# PCM1794_DAC_Breakout.net
KiCad netlist of a schematic drawn in EAGLE
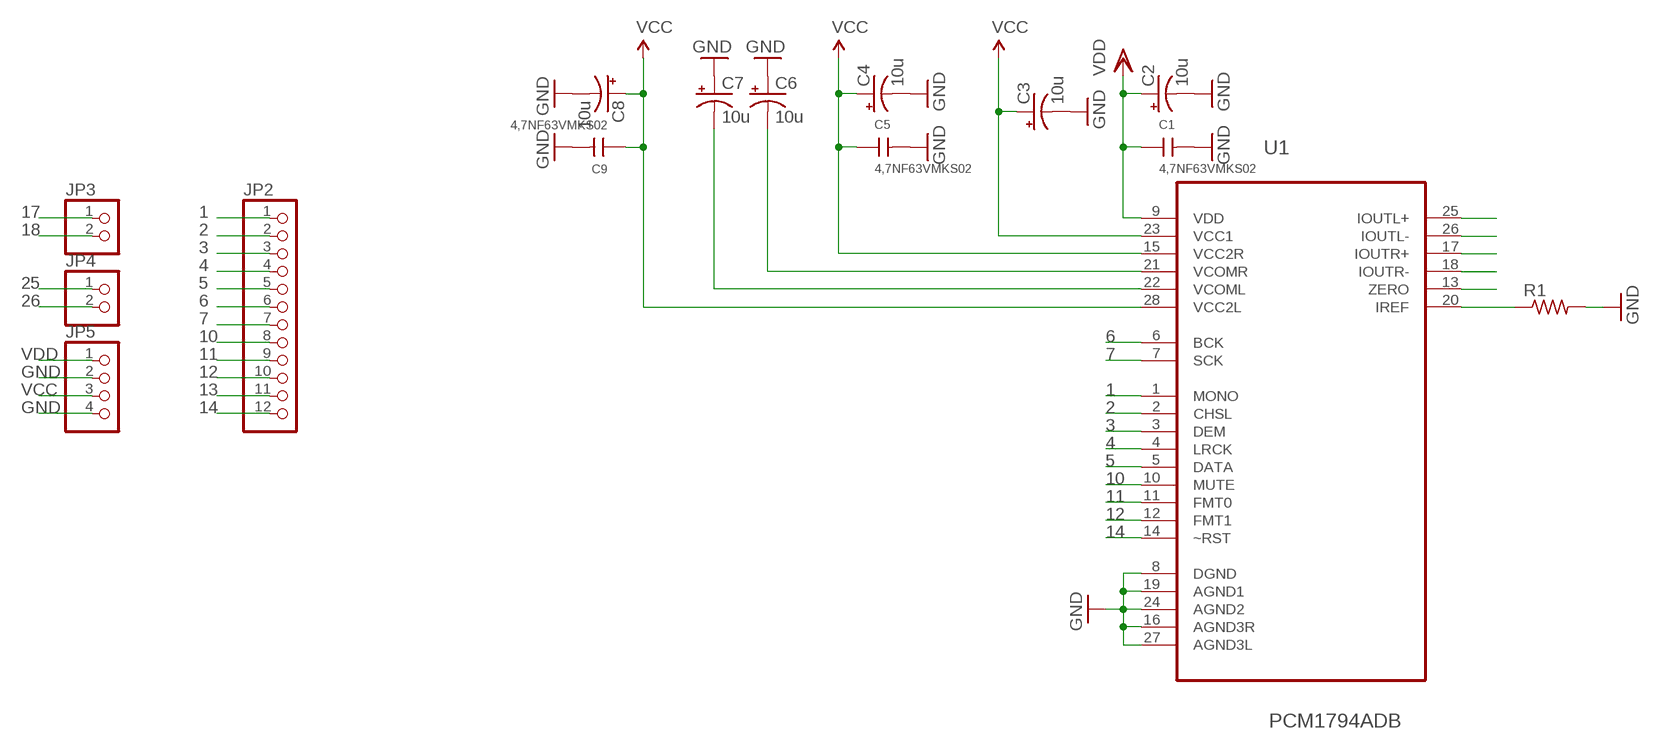
[diagram p0: schematic, sheet 1]

(export (version "E")
  (design (tool "Eeschema 10.0.6"))
  (components
    (comp (ref "C1")
      (value "4,7NF63VMKS02")
      (footprint "eagle-import:2,5X7,0RM2,5")
      (libsource (lib "eagle-import") (part "4,7NF63VMKS02"))
    )
    (comp (ref "C2")
      (value "10u")
      (footprint "eagle-import:E2,5-6")
      (libsource (lib "eagle-import") (part "CPOL-USE2.5-6"))
    )
    (comp (ref "C3")
      (value "10u")
      (footprint "eagle-import:E2,5-6")
      (libsource (lib "eagle-import") (part "CPOL-USE2.5-6"))
    )
    (comp (ref "C4")
      (value "10u")
      (footprint "eagle-import:E2,5-6")
      (libsource (lib "eagle-import") (part "CPOL-USE2.5-6"))
    )
    (comp (ref "C5")
      (value "4,7NF63VMKS02")
      (footprint "eagle-import:2,5X7,0RM2,5")
      (libsource (lib "eagle-import") (part "4,7NF63VMKS02"))
    )
    (comp (ref "C6")
      (value "10u")
      (footprint "eagle-import:E2,5-6")
      (libsource (lib "eagle-import") (part "CPOL-USE2.5-6"))
    )
    (comp (ref "C7")
      (value "10u")
      (footprint "eagle-import:E2,5-6")
      (libsource (lib "eagle-import") (part "CPOL-USE2.5-6"))
    )
    (comp (ref "C8")
      (value "10u")
      (footprint "eagle-import:E2,5-6")
      (libsource (lib "eagle-import") (part "CPOL-USE2.5-6"))
    )
    (comp (ref "C9")
      (value "4,7NF63VMKS02")
      (footprint "eagle-import:2,5X7,0RM2,5")
      (libsource (lib "eagle-import") (part "4,7NF63VMKS02"))
    )
    (comp (ref "JP2")
      (value "PINHD-1X12")
      (footprint "eagle-import:1X12")
      (libsource (lib "eagle-import") (part "PINHD-1X12"))
    )
    (comp (ref "JP3")
      (value "PINHD-1X2")
      (footprint "eagle-import:1X02")
      (libsource (lib "eagle-import") (part "PINHD-1X2"))
    )
    (comp (ref "JP4")
      (value "PINHD-1X2")
      (footprint "eagle-import:1X02")
      (libsource (lib "eagle-import") (part "PINHD-1X2"))
    )
    (comp (ref "JP5")
      (value "PINHD-1X4")
      (footprint "eagle-import:1X04")
      (libsource (lib "eagle-import") (part "PINHD-1X4"))
    )
    (comp (ref "R1")
      (value "R-US_R0603")
      (footprint "eagle-import:R0603")
      (libsource (lib "eagle-import") (part "R-US_R0603"))
    )
    (comp (ref "U1")
      (value "PCM1794ADB")
      (footprint "eagle-import:SOP65P780X200-28N")
      (libsource (lib "eagle-import") (part "PCM1794ADB"))
    )
  )
  (nets
    (net (code "1") (name "/1") (class "Default")
      (node (ref "JP2") (pin "1") (pinfunction "1_1") (pintype "passive"))
      (node (ref "U1") (pin "1") (pinfunction "MONO_1") (pintype "input"))
    )
    (net (code "2") (name "/2") (class "Default")
      (node (ref "JP2") (pin "2") (pinfunction "2_2") (pintype "passive"))
      (node (ref "U1") (pin "2") (pinfunction "CHSL_2") (pintype "input"))
    )
    (net (code "3") (name "/3") (class "Default")
      (node (ref "JP2") (pin "3") (pinfunction "3_3") (pintype "passive"))
      (node (ref "U1") (pin "3") (pinfunction "DEM_3") (pintype "input"))
    )
    (net (code "4") (name "/4") (class "Default")
      (node (ref "JP2") (pin "4") (pinfunction "4_4") (pintype "passive"))
      (node (ref "U1") (pin "4") (pinfunction "LRCK_4") (pintype "input"))
    )
    (net (code "5") (name "/5") (class "Default")
      (node (ref "JP2") (pin "5") (pinfunction "5_5") (pintype "passive"))
      (node (ref "U1") (pin "5") (pinfunction "DATA_5") (pintype "input"))
    )
    (net (code "6") (name "/6") (class "Default")
      (node (ref "JP2") (pin "6") (pinfunction "6_6") (pintype "passive"))
      (node (ref "U1") (pin "6") (pinfunction "BCK_6") (pintype "input"))
    )
    (net (code "7") (name "/7") (class "Default")
      (node (ref "JP2") (pin "7") (pinfunction "7_7") (pintype "passive"))
      (node (ref "U1") (pin "7") (pinfunction "SCK_7") (pintype "input"))
    )
    (net (code "8") (name "/10") (class "Default")
      (node (ref "JP2") (pin "8") (pinfunction "8_8") (pintype "passive"))
      (node (ref "U1") (pin "10") (pinfunction "MUTE_10") (pintype "input"))
    )
    (net (code "9") (name "/11") (class "Default")
      (node (ref "JP2") (pin "9") (pinfunction "9_9") (pintype "passive"))
      (node (ref "U1") (pin "11") (pinfunction "FMT0_11") (pintype "input"))
    )
    (net (code "10") (name "/12") (class "Default")
      (node (ref "JP2") (pin "10") (pinfunction "10_10") (pintype "passive"))
      (node (ref "U1") (pin "12") (pinfunction "FMT1_12") (pintype "input"))
    )
    (net (code "11") (name "/13") (class "Default")
      (node (ref "JP2") (pin "11") (pinfunction "11_11") (pintype "passive"))
      (node (ref "U1") (pin "13") (pinfunction "ZERO_13") (pintype "output"))
    )
    (net (code "12") (name "/14") (class "Default")
      (node (ref "JP2") (pin "12") (pinfunction "12_12") (pintype "passive"))
      (node (ref "U1") (pin "14") (pinfunction "~{RST}_14") (pintype "input"))
    )
    (net (code "13") (name "/17") (class "Default")
      (node (ref "JP3") (pin "1") (pinfunction "1_1") (pintype "passive"))
      (node (ref "U1") (pin "17") (pinfunction "IOUTR+_17") (pintype "output"))
    )
    (net (code "14") (name "/18") (class "Default")
      (node (ref "JP3") (pin "2") (pinfunction "2_2") (pintype "passive"))
      (node (ref "U1") (pin "18") (pinfunction "IOUTR-_18") (pintype "output"))
    )
    (net (code "15") (name "/25") (class "Default")
      (node (ref "JP4") (pin "1") (pinfunction "1_1") (pintype "passive"))
      (node (ref "U1") (pin "25") (pinfunction "IOUTL+_25") (pintype "output"))
    )
    (net (code "16") (name "/26") (class "Default")
      (node (ref "JP4") (pin "2") (pinfunction "2_2") (pintype "passive"))
      (node (ref "U1") (pin "26") (pinfunction "IOUTL-_26") (pintype "output"))
    )
    (net (code "17") (name "GND") (class "Default")
      (node (ref "C1") (pin "2") (pinfunction "2_2") (pintype "passive"))
      (node (ref "C2") (pin "-") (pinfunction "-_-") (pintype "passive"))
      (node (ref "C3") (pin "-") (pinfunction "-_-") (pintype "passive"))
      (node (ref "C4") (pin "-") (pinfunction "-_-") (pintype "passive"))
      (node (ref "C5") (pin "2") (pinfunction "2_2") (pintype "passive"))
      (node (ref "C6") (pin "+") (pinfunction "+_+") (pintype "passive"))
      (node (ref "C7") (pin "+") (pinfunction "+_+") (pintype "passive"))
      (node (ref "C8") (pin "-") (pinfunction "-_-") (pintype "passive"))
      (node (ref "C9") (pin "2") (pinfunction "2_2") (pintype "passive"))
      (node (ref "JP5") (pin "2") (pinfunction "2_2") (pintype "passive"))
      (node (ref "JP5") (pin "4") (pinfunction "4_4") (pintype "passive"))
      (node (ref "R1") (pin "2") (pinfunction "2_2") (pintype "passive"))
      (node (ref "U1") (pin "16") (pinfunction "AGND3R_16") (pintype "passive"))
      (node (ref "U1") (pin "19") (pinfunction "AGND1_19") (pintype "passive"))
      (node (ref "U1") (pin "24") (pinfunction "AGND2_24") (pintype "passive"))
      (node (ref "U1") (pin "27") (pinfunction "AGND3L_27") (pintype "passive"))
      (node (ref "U1") (pin "8") (pinfunction "DGND_8") (pintype "passive"))
    )
    (net (code "18") (name "Net-(U1-IREF)") (class "Default")
      (node (ref "R1") (pin "1") (pinfunction "1_1") (pintype "passive"))
      (node (ref "U1") (pin "20") (pinfunction "IREF_20") (pintype "output"))
    )
    (net (code "19") (name "Net-(U1-VCOML)") (class "Default")
      (node (ref "C7") (pin "-") (pinfunction "-_-") (pintype "passive"))
      (node (ref "U1") (pin "22") (pinfunction "VCOML_22") (pintype "input"))
    )
    (net (code "20") (name "Net-(U1-VCOMR)") (class "Default")
      (node (ref "C6") (pin "-") (pinfunction "-_-") (pintype "passive"))
      (node (ref "U1") (pin "21") (pinfunction "VCOMR_21") (pintype "input"))
    )
    (net (code "21") (name "VCC") (class "Default")
      (node (ref "C3") (pin "+") (pinfunction "+_+") (pintype "passive"))
      (node (ref "C4") (pin "+") (pinfunction "+_+") (pintype "passive"))
      (node (ref "C5") (pin "1") (pinfunction "1_1") (pintype "passive"))
      (node (ref "C8") (pin "+") (pinfunction "+_+") (pintype "passive"))
      (node (ref "C9") (pin "1") (pinfunction "1_1") (pintype "passive"))
      (node (ref "JP5") (pin "3") (pinfunction "3_3") (pintype "passive"))
      (node (ref "U1") (pin "15") (pinfunction "VCC2R_15") (pintype "power_in"))
      (node (ref "U1") (pin "23") (pinfunction "VCC1_23") (pintype "power_in"))
      (node (ref "U1") (pin "28") (pinfunction "VCC2L_28") (pintype "power_in"))
    )
    (net (code "22") (name "VDD") (class "Default")
      (node (ref "C1") (pin "1") (pinfunction "1_1") (pintype "passive"))
      (node (ref "C2") (pin "+") (pinfunction "+_+") (pintype "passive"))
      (node (ref "JP5") (pin "1") (pinfunction "1_1") (pintype "passive"))
      (node (ref "U1") (pin "9") (pinfunction "VDD_9") (pintype "power_in"))
    )
  )
)
